# snappergps_board_2_1_0.net
KiCad netlist of a schematic drawn in EAGLE
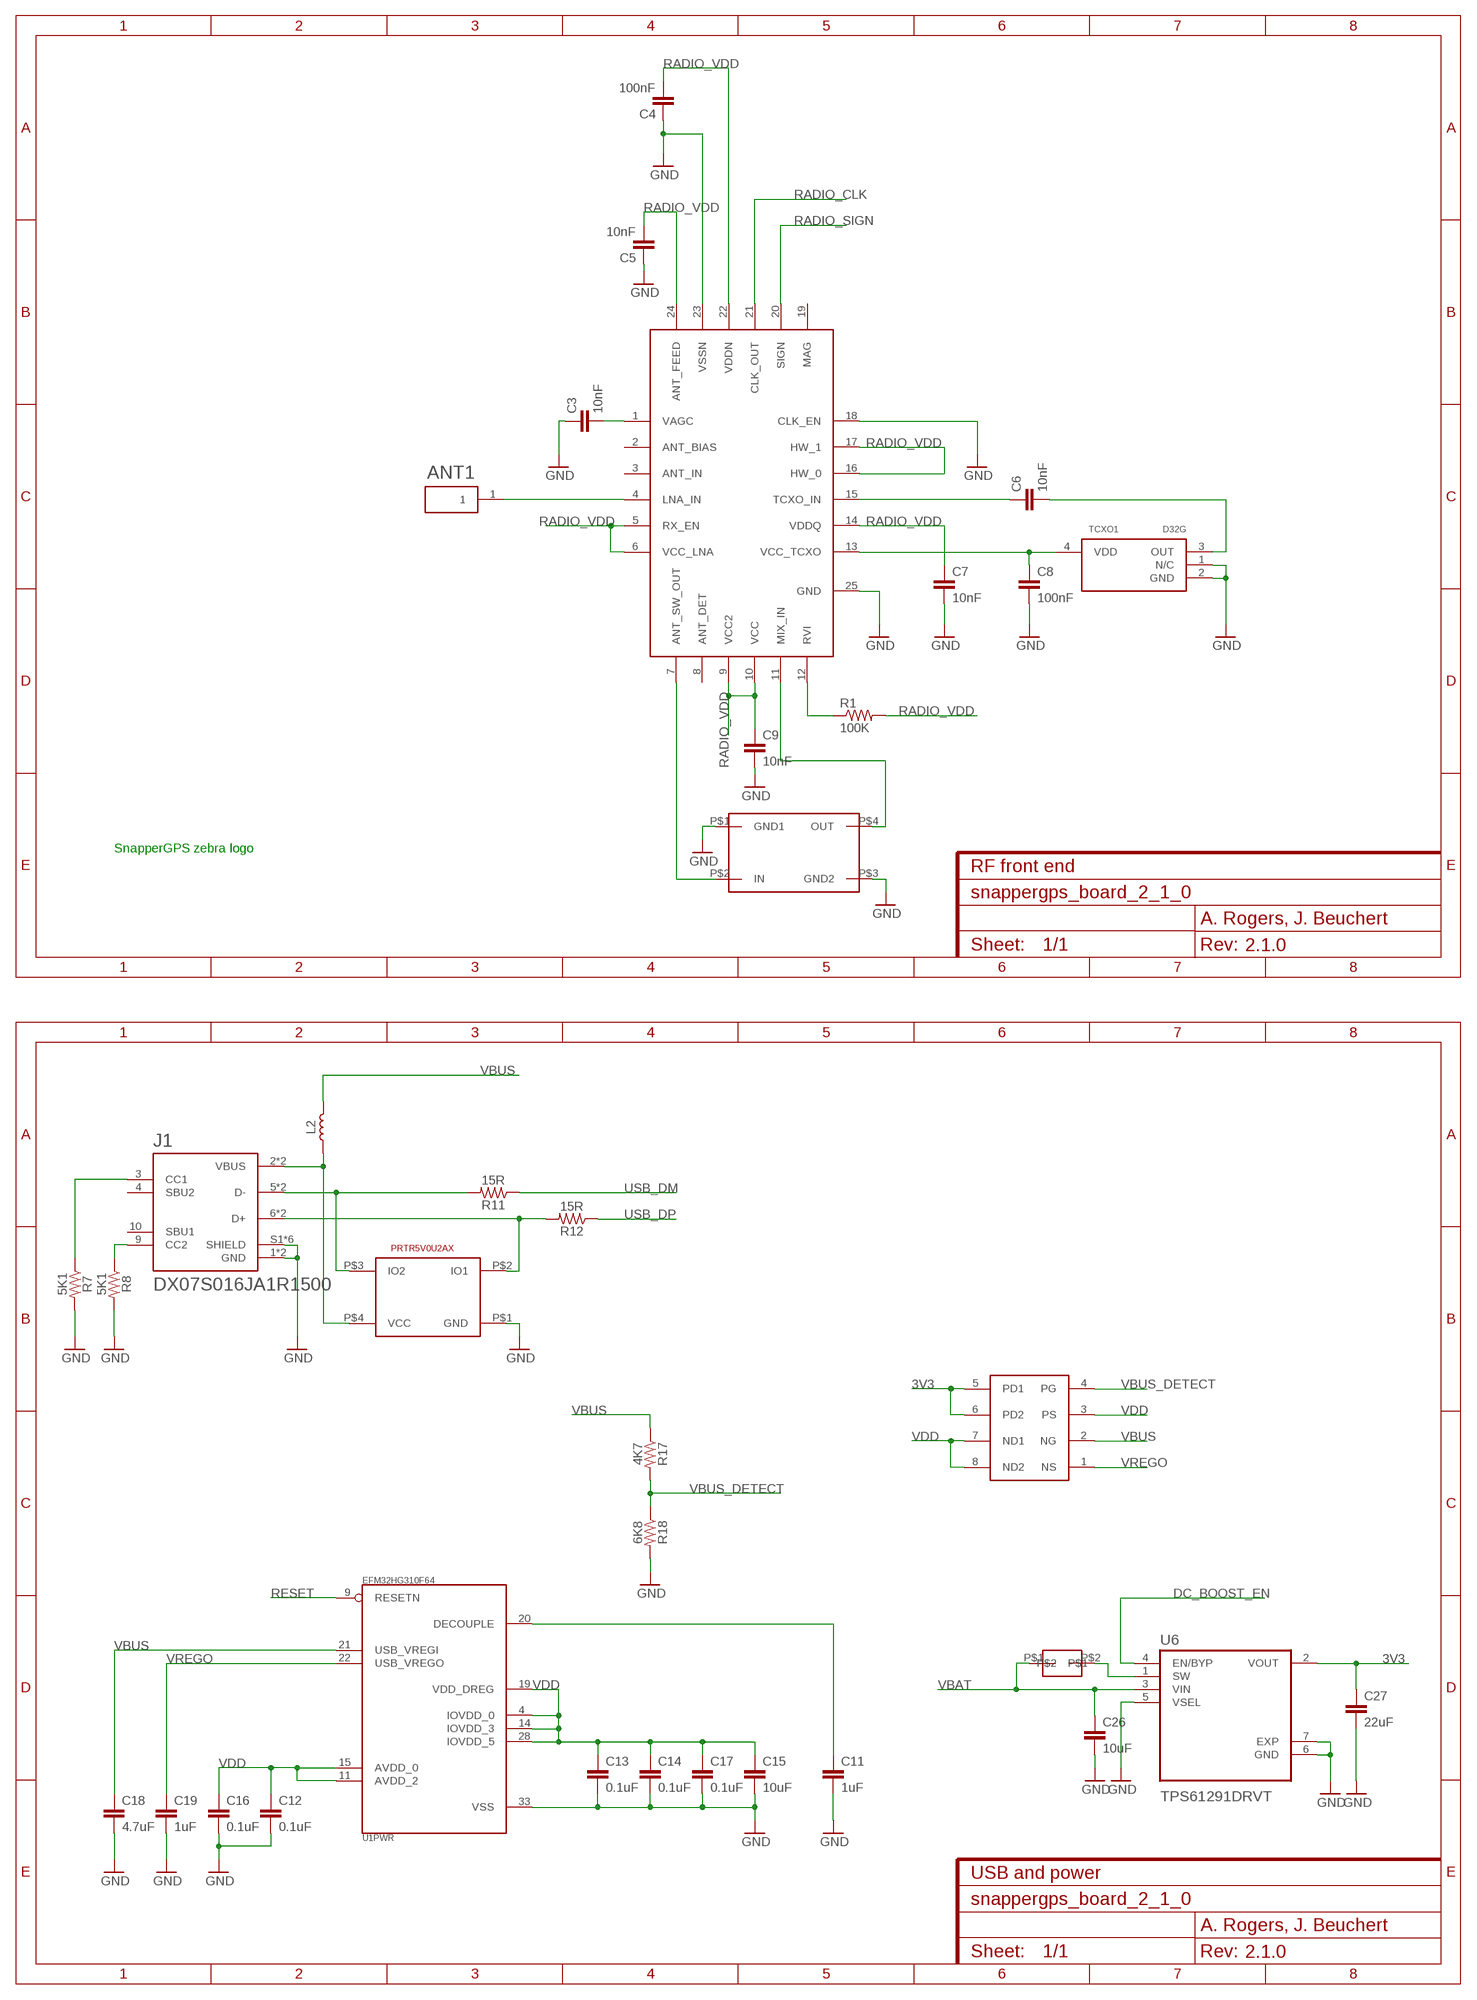
[diagram p0: schematic, sheet 1, part 1 of 2]
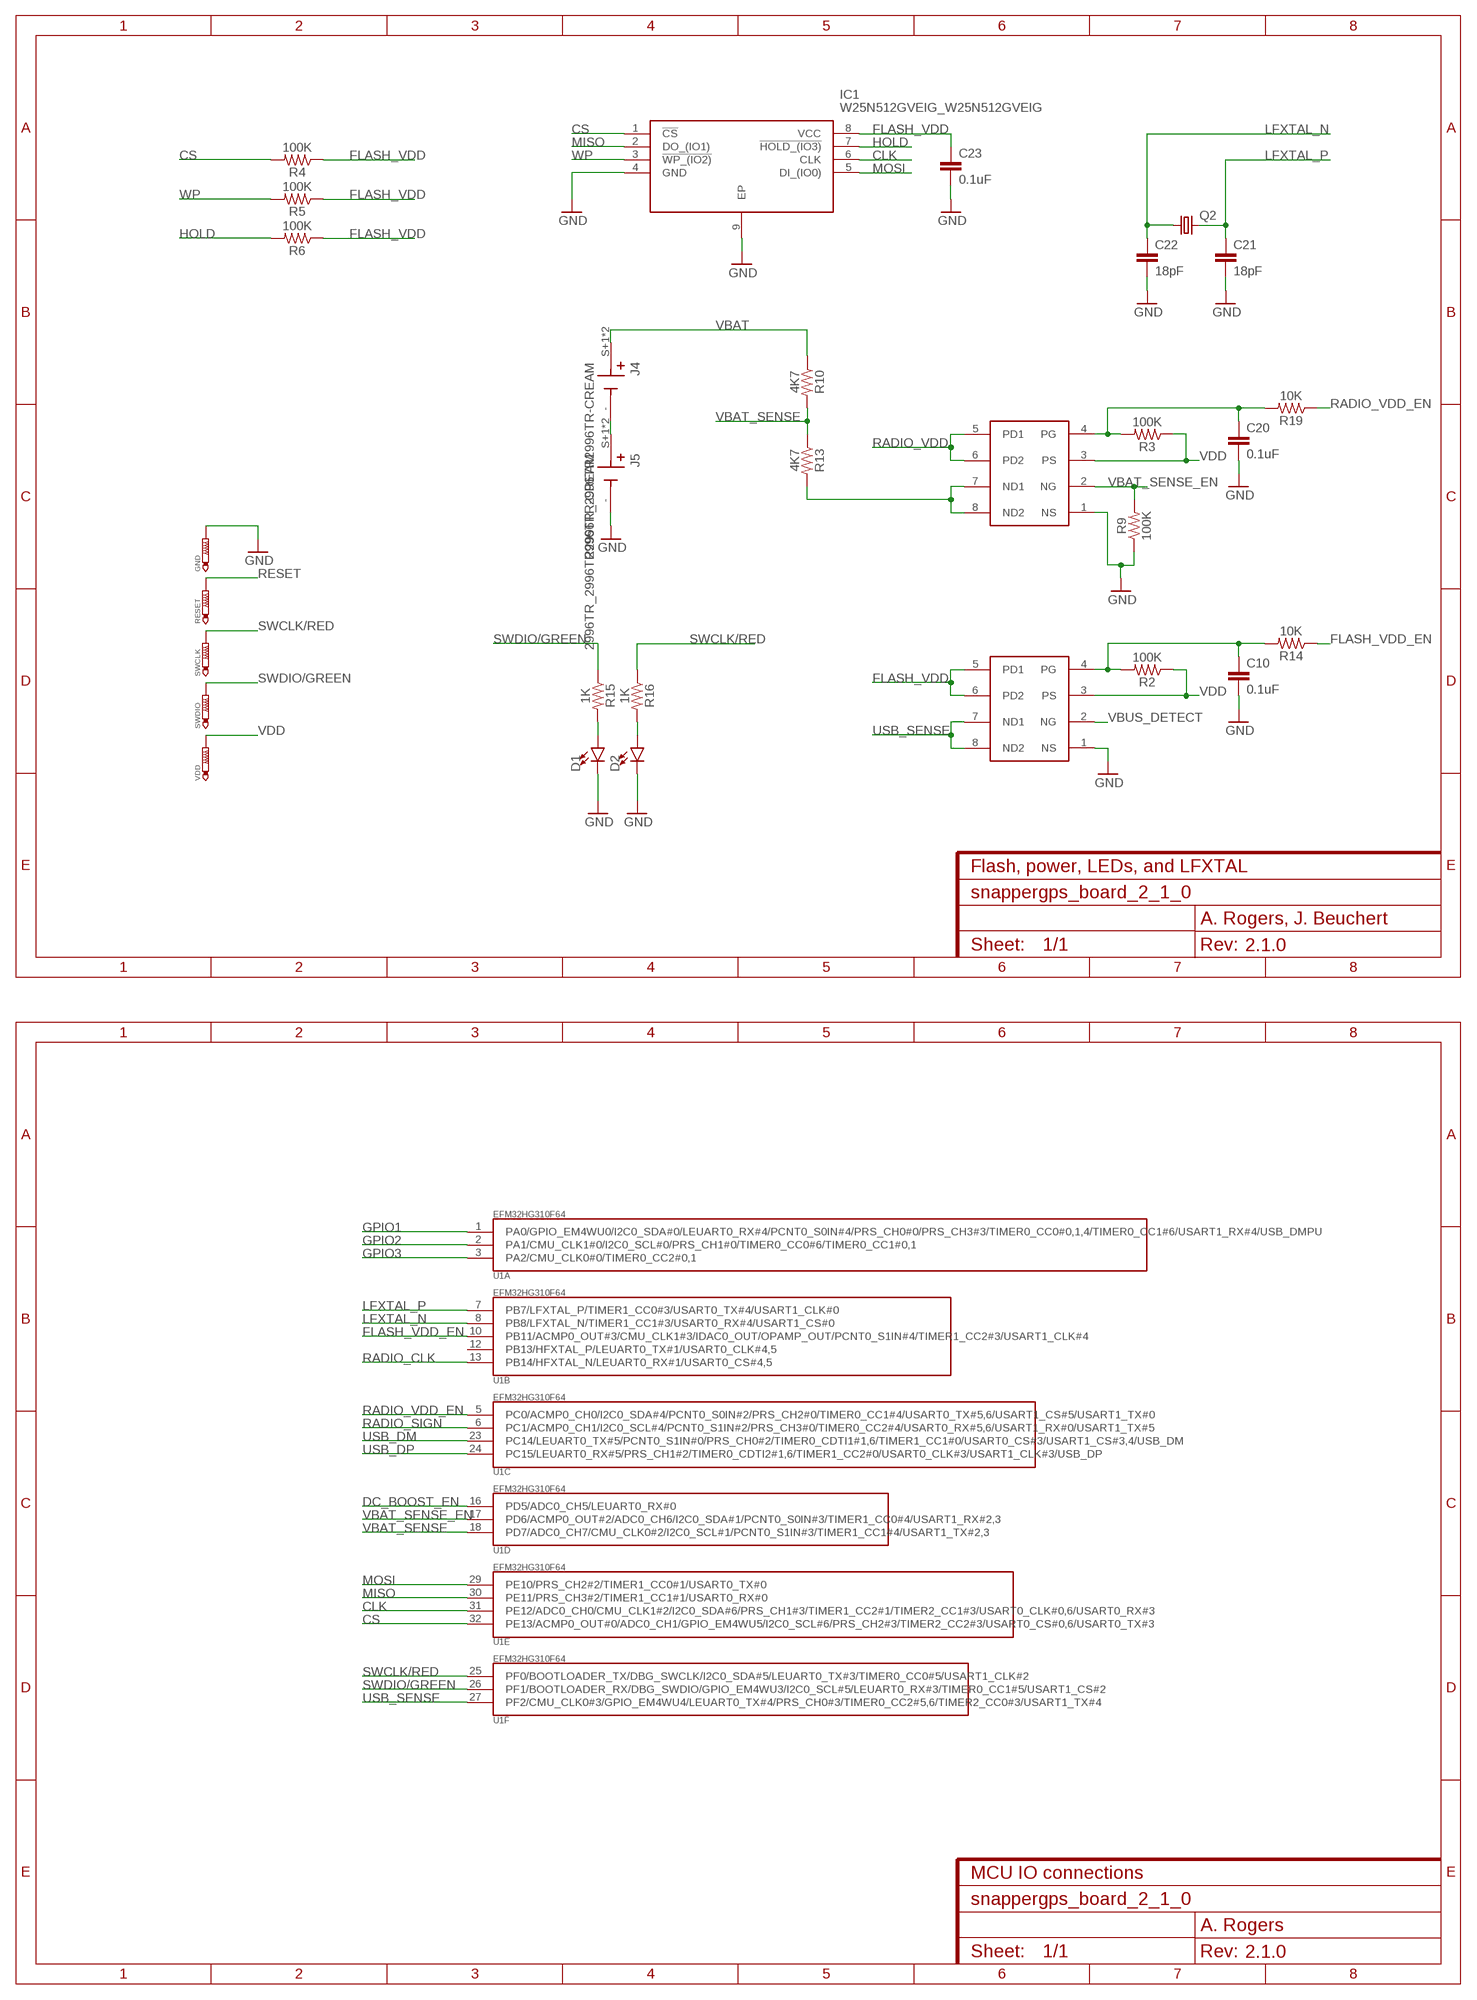
[diagram p1: schematic, sheet 1, part 2 of 2]

(export (version "E")
  (design (tool "Eeschema 10.0.6"))
  (components
    (comp (ref "ANT1")
      (value "GP.1575.25.2.A.02")
      (footprint "eagle-import:GP1575252A02")
      (fields (field (name "MOUSER_PART_NUMBER") "960-GP1575252A02"))
      (libsource (lib "eagle-import") (part "GP.1575.25.2.A.02"))
    )
    (comp (ref "C3")
      (value "10nF")
      (footprint "eagle-import:0402")
      (libsource (lib "eagle-import") (part "CAPACITOR_0402"))
    )
    (comp (ref "C4")
      (value "100nF")
      (footprint "eagle-import:0402")
      (libsource (lib "eagle-import") (part "CAPACITOR_0402"))
    )
    (comp (ref "C5")
      (value "10nF")
      (footprint "eagle-import:0402")
      (libsource (lib "eagle-import") (part "CAPACITOR_0402"))
    )
    (comp (ref "C6")
      (value "10nF")
      (footprint "eagle-import:0402")
      (libsource (lib "eagle-import") (part "CAPACITOR_0402"))
    )
    (comp (ref "C7")
      (value "10nF")
      (footprint "eagle-import:0402")
      (libsource (lib "eagle-import") (part "CAPACITOR_0402"))
    )
    (comp (ref "C8")
      (value "100nF")
      (footprint "eagle-import:0402")
      (libsource (lib "eagle-import") (part "CAPACITOR_0402"))
    )
    (comp (ref "C9")
      (value "10nF")
      (footprint "eagle-import:0402")
      (libsource (lib "eagle-import") (part "CAPACITOR_0402"))
    )
    (comp (ref "C10")
      (value "0.1uF")
      (footprint "eagle-import:0402")
      (libsource (lib "eagle-import") (part "CAPACITOR_0402"))
    )
    (comp (ref "C11")
      (value "1uF")
      (footprint "eagle-import:0603")
      (libsource (lib "eagle-import") (part "CAPACITOR_0603"))
    )
    (comp (ref "C12")
      (value "0.1uF")
      (footprint "eagle-import:0402")
      (libsource (lib "eagle-import") (part "CAPACITOR_0402"))
    )
    (comp (ref "C13")
      (value "0.1uF")
      (footprint "eagle-import:0402")
      (libsource (lib "eagle-import") (part "CAPACITOR_0402"))
    )
    (comp (ref "C14")
      (value "0.1uF")
      (footprint "eagle-import:0402")
      (libsource (lib "eagle-import") (part "CAPACITOR_0402"))
    )
    (comp (ref "C15")
      (value "10uF")
      (footprint "eagle-import:0603")
      (libsource (lib "eagle-import") (part "CAPACITOR_0603"))
    )
    (comp (ref "C16")
      (value "0.1uF")
      (footprint "eagle-import:0402")
      (libsource (lib "eagle-import") (part "CAPACITOR_0402"))
    )
    (comp (ref "C17")
      (value "0.1uF")
      (footprint "eagle-import:0402")
      (libsource (lib "eagle-import") (part "CAPACITOR_0402"))
    )
    (comp (ref "C18")
      (value "4.7uF")
      (footprint "eagle-import:0603")
      (libsource (lib "eagle-import") (part "CAPACITOR_0603"))
    )
    (comp (ref "C19")
      (value "1uF")
      (footprint "eagle-import:0603")
      (libsource (lib "eagle-import") (part "CAPACITOR_0603"))
    )
    (comp (ref "C20")
      (value "0.1uF")
      (footprint "eagle-import:0402")
      (libsource (lib "eagle-import") (part "CAPACITOR_0402"))
    )
    (comp (ref "C21")
      (value "18pF")
      (footprint "eagle-import:0402")
      (libsource (lib "eagle-import") (part "CAPACITOR_0402"))
    )
    (comp (ref "C22")
      (value "18pF")
      (footprint "eagle-import:0402")
      (libsource (lib "eagle-import") (part "CAPACITOR_0402"))
    )
    (comp (ref "C23")
      (value "0.1uF")
      (footprint "eagle-import:0402")
      (libsource (lib "eagle-import") (part "CAPACITOR_0402"))
    )
    (comp (ref "C26")
      (value "10uF")
      (footprint "eagle-import:C0603K")
      (libsource (lib "eagle-import") (part "C-EUC0603K"))
    )
    (comp (ref "C27")
      (value "22uF")
      (footprint "eagle-import:C0603K")
      (libsource (lib "eagle-import") (part "C-EUC0603K"))
    )
    (comp (ref "D1")
      (value "LED0603")
      (footprint "eagle-import:LED-0603")
      (libsource (lib "eagle-import") (part "LED0603"))
    )
    (comp (ref "D2")
      (value "LED0603")
      (footprint "eagle-import:LED-0603")
      (libsource (lib "eagle-import") (part "LED0603"))
    )
    (comp (ref "GND")
      (value "PTR1B1,27")
      (footprint "eagle-import:B1,27")
      (libsource (lib "eagle-import") (part "PTR1B1,27"))
    )
    (comp (ref "IC1")
      (value "W25N512GVEIG_W25N512GVEIG")
      (footprint "eagle-import:W25N512GVEIG_SON127P800X600X80-9N")
      (fields
        (field (name "MANUFACTURER_PART_NUMBER") "W25N512GVEIG")
        (field (name "MOUSER_PART_NUMBER") "454-W25N512GVEIG")
      )
      (libsource (lib "eagle-import") (part "W25N512GVEIG_W25N512GVEIG"))
    )
    (comp (ref "J1")
      (value "DX07S016JA1R1500")
      (footprint "eagle-import:JAE_DX07S016JA1R1500")
      (fields (field (name "MF") "JAE Electronics"))
      (libsource (lib "eagle-import") (part "DX07S016JA1R1500"))
    )
    (comp (ref "J4")
      (value "2996TR_2996TR2996TR-CREAM")
      (footprint "eagle-import:2996TR_BAT_2996TR")
      (fields (field (name "MF") "Keystone Electronics") (field (name "MP") "2996TR"))
      (libsource (lib "eagle-import") (part "2996TR_2996TR2996TR-CREAM"))
    )
    (comp (ref "J5")
      (value "2996TR_2996TR2996TR-CREAM")
      (footprint "eagle-import:2996TR_BAT_2996TR")
      (fields (field (name "MF") "Keystone Electronics") (field (name "MP") "2996TR"))
      (libsource (lib "eagle-import") (part "2996TR_2996TR2996TR-CREAM"))
    )
    (comp (ref "L2")
      (value "INDUCTOR")
      (footprint "eagle-import:0402")
      (libsource (lib "eagle-import") (part "INDUCTOR"))
    )
    (comp (ref "Q1")
      (value "TT8M1TRAMANDA")
      (footprint "eagle-import:AMANDA_TSST8")
      (libsource (lib "eagle-import") (part "TT8M1TRAMANDA"))
    )
    (comp (ref "Q2")
      (value "CRYSTAL_JTX310")
      (footprint "eagle-import:3.2X1.5")
      (libsource (lib "eagle-import") (part "CRYSTAL_JTX310"))
    )
    (comp (ref "Q3")
      (value "TT8M1TRAMANDA")
      (footprint "eagle-import:AMANDA_TSST8")
      (libsource (lib "eagle-import") (part "TT8M1TRAMANDA"))
    )
    (comp (ref "Q4")
      (value "TT8M1TRAMANDA")
      (footprint "eagle-import:AMANDA_TSST8")
      (libsource (lib "eagle-import") (part "TT8M1TRAMANDA"))
    )
    (comp (ref "R1")
      (value "100K")
      (footprint "eagle-import:0402")
      (libsource (lib "eagle-import") (part "RESISTOR_0402"))
    )
    (comp (ref "R2")
      (value "100K")
      (footprint "eagle-import:0402")
      (libsource (lib "eagle-import") (part "RESISTOR_0402"))
    )
    (comp (ref "R3")
      (value "100K")
      (footprint "eagle-import:0402")
      (libsource (lib "eagle-import") (part "RESISTOR_0402"))
    )
    (comp (ref "R4")
      (value "100K")
      (footprint "eagle-import:0402")
      (libsource (lib "eagle-import") (part "RESISTOR_0402"))
    )
    (comp (ref "R5")
      (value "100K")
      (footprint "eagle-import:0402")
      (libsource (lib "eagle-import") (part "RESISTOR_0402"))
    )
    (comp (ref "R6")
      (value "100K")
      (footprint "eagle-import:0402")
      (libsource (lib "eagle-import") (part "RESISTOR_0402"))
    )
    (comp (ref "R7")
      (value "5K1")
      (footprint "eagle-import:0402")
      (libsource (lib "eagle-import") (part "RESISTOR_0402"))
    )
    (comp (ref "R8")
      (value "5K1")
      (footprint "eagle-import:0402")
      (libsource (lib "eagle-import") (part "RESISTOR_0402"))
    )
    (comp (ref "R9")
      (value "100K")
      (footprint "eagle-import:0402")
      (libsource (lib "eagle-import") (part "RESISTOR_0402"))
    )
    (comp (ref "R10")
      (value "4K7")
      (footprint "eagle-import:0402")
      (libsource (lib "eagle-import") (part "RESISTOR_0402"))
    )
    (comp (ref "R11")
      (value "15R")
      (footprint "eagle-import:0402")
      (libsource (lib "eagle-import") (part "RESISTOR_0402"))
    )
    (comp (ref "R12")
      (value "15R")
      (footprint "eagle-import:0402")
      (libsource (lib "eagle-import") (part "RESISTOR_0402"))
    )
    (comp (ref "R13")
      (value "4K7")
      (footprint "eagle-import:0402")
      (libsource (lib "eagle-import") (part "RESISTOR_0402"))
    )
    (comp (ref "R14")
      (value "10K")
      (footprint "eagle-import:0402")
      (libsource (lib "eagle-import") (part "RESISTOR_0402"))
    )
    (comp (ref "R15")
      (value "1K")
      (footprint "eagle-import:0402")
      (libsource (lib "eagle-import") (part "RESISTOR_0402"))
    )
    (comp (ref "R16")
      (value "1K")
      (footprint "eagle-import:0402")
      (libsource (lib "eagle-import") (part "RESISTOR_0402"))
    )
    (comp (ref "R17")
      (value "4K7")
      (footprint "eagle-import:0402")
      (libsource (lib "eagle-import") (part "RESISTOR_0402"))
    )
    (comp (ref "R18")
      (value "6K8")
      (footprint "eagle-import:0402")
      (libsource (lib "eagle-import") (part "RESISTOR_0402"))
    )
    (comp (ref "R19")
      (value "10K")
      (footprint "eagle-import:0402")
      (libsource (lib "eagle-import") (part "RESISTOR_0402"))
    )
    (comp (ref "RESET")
      (value "PTR1B1,27")
      (footprint "eagle-import:B1,27")
      (libsource (lib "eagle-import") (part "PTR1B1,27"))
    )
    (comp (ref "SAW1")
      (value "SAW_FILTER")
      (footprint "eagle-import:SAW_FILTER")
      (libsource (lib "eagle-import") (part "SAW_FILTER"))
    )
    (comp (ref "SWCLK")
      (value "PTR1B1,27")
      (footprint "eagle-import:B1,27")
      (libsource (lib "eagle-import") (part "PTR1B1,27"))
    )
    (comp (ref "SWDIO")
      (value "PTR1B1,27")
      (footprint "eagle-import:B1,27")
      (libsource (lib "eagle-import") (part "PTR1B1,27"))
    )
    (comp (ref "TCXO1")
      (value "D32G")
      (footprint "eagle-import:D32G")
      (libsource (lib "eagle-import") (part "D32G"))
    )
    (comp (ref "U1")
      (value "EFM32HG310F64")
      (footprint "eagle-import:QFN32")
      (libsource (lib "eagle-import") (part "EFM32HG310F64"))
    )
    (comp (ref "U2")
      (value "RF_CIRCUIT-SE4150L")
      (footprint "eagle-import:QFN50P400X400X90-25N")
      (libsource (lib "eagle-import") (part "RF_CIRCUIT-SE4150L"))
    )
    (comp (ref "U3")
      (value "TVS_DIODE-PRTR5V0U2AX")
      (footprint "eagle-import:TVS_DIODE-PRTR5V0U2AX")
      (libsource (lib "eagle-import") (part "TVS_DIODE-PRTR5V0U2AX"))
    )
    (comp (ref "U6")
      (value "TPS61291DRVT")
      (footprint "eagle-import:SON65P200X200X80-7N")
      (fields (field (name "MF") "Texas Instruments"))
      (libsource (lib "eagle-import") (part "TPS61291DRVT"))
    )
    (comp (ref "U7")
      (value "MDMK2020T3R3MM")
      (footprint "eagle-import:MDMK2020T3R3MM")
      (libsource (lib "eagle-import") (part "MDMK2020T3R3MM"))
    )
    (comp (ref "VDD")
      (value "PTR1B1,27")
      (footprint "eagle-import:B1,27")
      (libsource (lib "eagle-import") (part "PTR1B1,27"))
    )
  )
  (nets
    (net (code "1") (name "/3V3") (class "Default")
      (node (ref "C27") (pin "1") (pinfunction "1_1") (pintype "passive"))
      (node (ref "Q4") (pin "5") (pinfunction "PD1_5") (pintype "bidirectional"))
      (node (ref "Q4") (pin "6") (pinfunction "PD2_6") (pintype "bidirectional"))
      (node (ref "U6") (pin "2") (pinfunction "VOUT_2") (pintype "output"))
    )
    (net (code "2") (name "/CLK") (class "Default")
      (node (ref "IC1") (pin "6") (pinfunction "CLK_6") (pintype "bidirectional"))
      (node (ref "U1") (pin "31") (pinfunction "PE12/ADC0_CH0/CMU_CLK1#2/I2C0_SDA#6/PRS_CH1#3/TIMER1_CC2#1/TIMER2_CC1#3/USART0_CLK#0,6/USART0_RX#3_31") (pintype "bidirectional"))
    )
    (net (code "3") (name "/CS") (class "Default")
      (node (ref "IC1") (pin "1") (pinfunction "~{CS}_1") (pintype "bidirectional"))
      (node (ref "R4") (pin "2") (pinfunction "2_2") (pintype "passive"))
      (node (ref "U1") (pin "32") (pinfunction "PE13/ACMP0_OUT#0/ADC0_CH1/GPIO_EM4WU5/I2C0_SCL#6/PRS_CH2#3/TIMER2_CC2#3/USART0_CS#0,6/USART0_TX#3_32") (pintype "bidirectional"))
    )
    (net (code "4") (name "/DC_BOOST_EN") (class "Default")
      (node (ref "U1") (pin "16") (pinfunction "PD5/ADC0_CH5/LEUART0_RX#0_16") (pintype "bidirectional"))
      (node (ref "U6") (pin "4") (pinfunction "EN/BYP_4") (pintype "input"))
    )
    (net (code "5") (name "/FLASH_VDD") (class "Default")
      (node (ref "C23") (pin "1") (pinfunction "1_1") (pintype "passive"))
      (node (ref "IC1") (pin "8") (pinfunction "VCC_8") (pintype "bidirectional"))
      (node (ref "Q3") (pin "5") (pinfunction "PD1_5") (pintype "bidirectional"))
      (node (ref "Q3") (pin "6") (pinfunction "PD2_6") (pintype "bidirectional"))
      (node (ref "R4") (pin "1") (pinfunction "1_1") (pintype "passive"))
      (node (ref "R5") (pin "1") (pinfunction "1_1") (pintype "passive"))
      (node (ref "R6") (pin "1") (pinfunction "1_1") (pintype "passive"))
    )
    (net (code "6") (name "/FLASH_VDD_EN") (class "Default")
      (node (ref "R14") (pin "1") (pinfunction "1_1") (pintype "passive"))
      (node (ref "U1") (pin "10") (pinfunction "PB11/ACMP0_OUT#3/CMU_CLK1#3/IDAC0_OUT/OPAMP_OUT/PCNT0_S1IN#4/TIMER1_CC2#3/USART1_CLK#4_10") (pintype "bidirectional"))
    )
    (net (code "7") (name "/GPIO1") (class "Default")
      (node (ref "U1") (pin "1") (pinfunction "PA0/GPIO_EM4WU0/I2C0_SDA#0/LEUART0_RX#4/PCNT0_S0IN#4/PRS_CH0#0/PRS_CH3#3/TIMER0_CC0#0,1,4/TIMER0_CC1#6/USART1_RX#4/USB_DMPU_1") (pintype "bidirectional"))
    )
    (net (code "8") (name "/GPIO2") (class "Default")
      (node (ref "U1") (pin "2") (pinfunction "PA1/CMU_CLK1#0/I2C0_SCL#0/PRS_CH1#0/TIMER0_CC0#6/TIMER0_CC1#0,1_2") (pintype "bidirectional"))
    )
    (net (code "9") (name "/GPIO3") (class "Default")
      (node (ref "U1") (pin "3") (pinfunction "PA2/CMU_CLK0#0/TIMER0_CC2#0,1_3") (pintype "bidirectional"))
    )
    (net (code "10") (name "/HOLD") (class "Default")
      (node (ref "IC1") (pin "7") (pinfunction "~{HOLD_(IO3})_7") (pintype "bidirectional"))
      (node (ref "R6") (pin "2") (pinfunction "2_2") (pintype "passive"))
    )
    (net (code "11") (name "/LFXTAL_N") (class "Default")
      (node (ref "C22") (pin "1") (pinfunction "1_1") (pintype "passive"))
      (node (ref "Q2") (pin "1") (pinfunction "1_1") (pintype "passive"))
      (node (ref "U1") (pin "8") (pinfunction "PB8/LFXTAL_N/TIMER1_CC1#3/USART0_RX#4/USART1_CS#0_8") (pintype "bidirectional"))
    )
    (net (code "12") (name "/LFXTAL_P") (class "Default")
      (node (ref "C21") (pin "1") (pinfunction "1_1") (pintype "passive"))
      (node (ref "Q2") (pin "2") (pinfunction "2_2") (pintype "passive"))
      (node (ref "U1") (pin "7") (pinfunction "PB7/LFXTAL_P/TIMER1_CC0#3/USART0_TX#4/USART1_CLK#0_7") (pintype "bidirectional"))
    )
    (net (code "13") (name "/MISO") (class "Default")
      (node (ref "IC1") (pin "2") (pinfunction "DO_(IO1)_2") (pintype "bidirectional"))
      (node (ref "U1") (pin "30") (pinfunction "PE11/PRS_CH3#2/TIMER1_CC1#1/USART0_RX#0_30") (pintype "bidirectional"))
    )
    (net (code "14") (name "/MOSI") (class "Default")
      (node (ref "IC1") (pin "5") (pinfunction "DI_(IO0)_5") (pintype "bidirectional"))
      (node (ref "U1") (pin "29") (pinfunction "PE10/PRS_CH2#2/TIMER1_CC0#1/USART0_TX#0_29") (pintype "bidirectional"))
    )
    (net (code "15") (name "/RADIO_CLK") (class "Default")
      (node (ref "U1") (pin "13") (pinfunction "PB14/HFXTAL_N/LEUART0_RX#1/USART0_CS#4,5_13") (pintype "bidirectional"))
      (node (ref "U2") (pin "21") (pinfunction "CLK_OUT_21") (pintype "bidirectional"))
    )
    (net (code "16") (name "/RADIO_SIGN") (class "Default")
      (node (ref "U1") (pin "6") (pinfunction "PC1/ACMP0_CH1/I2C0_SCL#4/PCNT0_S1IN#2/PRS_CH3#0/TIMER0_CC2#4/USART0_RX#5,6/USART1_RX#0/USART1_TX#5_6") (pintype "bidirectional"))
      (node (ref "U2") (pin "20") (pinfunction "SIGN_20") (pintype "bidirectional"))
    )
    (net (code "17") (name "/RADIO_VDD") (class "Default")
      (node (ref "C4") (pin "2") (pinfunction "2_2") (pintype "passive"))
      (node (ref "C5") (pin "2") (pinfunction "2_2") (pintype "passive"))
      (node (ref "C7") (pin "1") (pinfunction "1_1") (pintype "passive"))
      (node (ref "C9") (pin "1") (pinfunction "1_1") (pintype "passive"))
      (node (ref "Q1") (pin "5") (pinfunction "PD1_5") (pintype "bidirectional"))
      (node (ref "Q1") (pin "6") (pinfunction "PD2_6") (pintype "bidirectional"))
      (node (ref "R1") (pin "2") (pinfunction "2_2") (pintype "passive"))
      (node (ref "U2") (pin "10") (pinfunction "VCC_10") (pintype "bidirectional"))
      (node (ref "U2") (pin "14") (pinfunction "VDDQ_14") (pintype "bidirectional"))
      (node (ref "U2") (pin "16") (pinfunction "HW_0_16") (pintype "bidirectional"))
      (node (ref "U2") (pin "17") (pinfunction "HW_1_17") (pintype "bidirectional"))
      (node (ref "U2") (pin "22") (pinfunction "VDDN_22") (pintype "bidirectional"))
      (node (ref "U2") (pin "24") (pinfunction "ANT_FEED_24") (pintype "bidirectional"))
      (node (ref "U2") (pin "5") (pinfunction "RX_EN_5") (pintype "bidirectional"))
      (node (ref "U2") (pin "6") (pinfunction "VCC_LNA_6") (pintype "bidirectional"))
      (node (ref "U2") (pin "9") (pinfunction "VCC2_9") (pintype "bidirectional"))
    )
    (net (code "18") (name "/RADIO_VDD_EN") (class "Default")
      (node (ref "R19") (pin "1") (pinfunction "1_1") (pintype "passive"))
      (node (ref "U1") (pin "5") (pinfunction "PC0/ACMP0_CH0/I2C0_SDA#4/PCNT0_S0IN#2/PRS_CH2#0/TIMER0_CC1#4/USART0_TX#5,6/USART1_CS#5/USART1_TX#0_5") (pintype "bidirectional"))
    )
    (net (code "19") (name "/RESET") (class "Default")
      (node (ref "RESET") (pin "TP") (pinfunction "TP_TP") (pintype "input"))
      (node (ref "U1") (pin "9") (pinfunction "RESETN_9") (pintype "passive"))
    )
    (net (code "20") (name "/SWCLK{slash}RED") (class "Default")
      (node (ref "R16") (pin "1") (pinfunction "1_1") (pintype "passive"))
      (node (ref "SWCLK") (pin "TP") (pinfunction "TP_TP") (pintype "input"))
      (node (ref "U1") (pin "25") (pinfunction "PF0/BOOTLOADER_TX/DBG_SWCLK/I2C0_SDA#5/LEUART0_TX#3/TIMER0_CC0#5/USART1_CLK#2_25") (pintype "bidirectional"))
    )
    (net (code "21") (name "/SWDIO{slash}GREEN") (class "Default")
      (node (ref "R15") (pin "1") (pinfunction "1_1") (pintype "passive"))
      (node (ref "SWDIO") (pin "TP") (pinfunction "TP_TP") (pintype "input"))
      (node (ref "U1") (pin "26") (pinfunction "PF1/BOOTLOADER_RX/DBG_SWDIO/GPIO_EM4WU3/I2C0_SCL#5/LEUART0_RX#3/TIMER0_CC1#5/USART1_CS#2_26") (pintype "bidirectional"))
    )
    (net (code "22") (name "/USB_DM") (class "Default")
      (node (ref "R11") (pin "1") (pinfunction "1_1") (pintype "passive"))
      (node (ref "U1") (pin "23") (pinfunction "PC14/LEUART0_TX#5/PCNT0_S1IN#0/PRS_CH0#2/TIMER0_CDTI1#1,6/TIMER1_CC1#0/USART0_CS#3/USART1_CS#3,4/USB_DM_23") (pintype "bidirectional"))
    )
    (net (code "23") (name "/USB_DP") (class "Default")
      (node (ref "R12") (pin "1") (pinfunction "1_1") (pintype "passive"))
      (node (ref "U1") (pin "24") (pinfunction "PC15/LEUART0_RX#5/PRS_CH1#2/TIMER0_CDTI2#1,6/TIMER1_CC2#0/USART0_CLK#3/USART1_CLK#3/USB_DP_24") (pintype "bidirectional"))
    )
    (net (code "24") (name "/USB_SENSE") (class "Default")
      (node (ref "Q3") (pin "7") (pinfunction "ND1_7") (pintype "bidirectional"))
      (node (ref "Q3") (pin "8") (pinfunction "ND2_8") (pintype "bidirectional"))
      (node (ref "U1") (pin "27") (pinfunction "PF2/CMU_CLK0#3/GPIO_EM4WU4/LEUART0_TX#4/PRS_CH0#3/TIMER0_CC2#5,6/TIMER2_CC0#3/USART1_TX#4_27") (pintype "bidirectional"))
    )
    (net (code "25") (name "/VBAT") (class "Default")
      (node (ref "C26") (pin "1") (pinfunction "1_1") (pintype "passive"))
      (node (ref "J4") (pin "S+1") (pinfunction "+_S+1") (pintype "passive"))
      (node (ref "J4") (pin "S+2") (pinfunction "+_S+2") (pintype "passive"))
      (node (ref "R10") (pin "1") (pinfunction "1_1") (pintype "passive"))
      (node (ref "U6") (pin "3") (pinfunction "VIN_3") (pintype "input"))
      (node (ref "U7") (pin "P$1") (pinfunction "P$1_P$1") (pintype "bidirectional"))
    )
    (net (code "26") (name "/VBAT_SENSE") (class "Default")
      (node (ref "R10") (pin "2") (pinfunction "2_2") (pintype "passive"))
      (node (ref "R13") (pin "1") (pinfunction "1_1") (pintype "passive"))
      (node (ref "U1") (pin "18") (pinfunction "PD7/ADC0_CH7/CMU_CLK0#2/I2C0_SCL#1/PCNT0_S1IN#3/TIMER1_CC1#4/USART1_TX#2,3_18") (pintype "bidirectional"))
    )
    (net (code "27") (name "/VBAT_SENSE_EN") (class "Default")
      (node (ref "Q1") (pin "2") (pinfunction "NG_2") (pintype "bidirectional"))
      (node (ref "R9") (pin "2") (pinfunction "2_2") (pintype "passive"))
      (node (ref "U1") (pin "17") (pinfunction "PD6/ACMP0_OUT#2/ADC0_CH6/I2C0_SDA#1/PCNT0_S0IN#3/TIMER1_CC0#4/USART1_RX#2,3_17") (pintype "bidirectional"))
    )
    (net (code "28") (name "/VBUS") (class "Default")
      (node (ref "C18") (pin "1") (pinfunction "1_1") (pintype "passive"))
      (node (ref "L2") (pin "2") (pinfunction "2_2") (pintype "passive"))
      (node (ref "Q4") (pin "2") (pinfunction "NG_2") (pintype "bidirectional"))
      (node (ref "R17") (pin "1") (pinfunction "1_1") (pintype "passive"))
      (node (ref "U1") (pin "21") (pinfunction "USB_VREGI_21") (pintype "power_in"))
    )
    (net (code "29") (name "/VBUS_DETECT") (class "Default")
      (node (ref "Q3") (pin "2") (pinfunction "NG_2") (pintype "bidirectional"))
      (node (ref "Q4") (pin "4") (pinfunction "PG_4") (pintype "bidirectional"))
      (node (ref "R17") (pin "2") (pinfunction "2_2") (pintype "passive"))
      (node (ref "R18") (pin "1") (pinfunction "1_1") (pintype "passive"))
    )
    (net (code "30") (name "/VDD") (class "Default")
      (node (ref "C12") (pin "1") (pinfunction "1_1") (pintype "passive"))
      (node (ref "C13") (pin "1") (pinfunction "1_1") (pintype "passive"))
      (node (ref "C14") (pin "1") (pinfunction "1_1") (pintype "passive"))
      (node (ref "C15") (pin "1") (pinfunction "1_1") (pintype "passive"))
      (node (ref "C16") (pin "1") (pinfunction "1_1") (pintype "passive"))
      (node (ref "C17") (pin "1") (pinfunction "1_1") (pintype "passive"))
      (node (ref "Q1") (pin "3") (pinfunction "PS_3") (pintype "bidirectional"))
      (node (ref "Q3") (pin "3") (pinfunction "PS_3") (pintype "bidirectional"))
      (node (ref "Q4") (pin "3") (pinfunction "PS_3") (pintype "bidirectional"))
      (node (ref "Q4") (pin "7") (pinfunction "ND1_7") (pintype "bidirectional"))
      (node (ref "Q4") (pin "8") (pinfunction "ND2_8") (pintype "bidirectional"))
      (node (ref "R2") (pin "1") (pinfunction "1_1") (pintype "passive"))
      (node (ref "R3") (pin "1") (pinfunction "1_1") (pintype "passive"))
      (node (ref "U1") (pin "11") (pinfunction "AVDD_2_11") (pintype "power_in"))
      (node (ref "U1") (pin "14") (pinfunction "IOVDD_3_14") (pintype "power_in"))
      (node (ref "U1") (pin "15") (pinfunction "AVDD_0_15") (pintype "power_in"))
      (node (ref "U1") (pin "19") (pinfunction "VDD_DREG_19") (pintype "power_in"))
      (node (ref "U1") (pin "28") (pinfunction "IOVDD_5_28") (pintype "power_in"))
      (node (ref "U1") (pin "4") (pinfunction "IOVDD_0_4") (pintype "power_in"))
      (node (ref "VDD") (pin "TP") (pinfunction "TP_TP") (pintype "input"))
    )
    (net (code "31") (name "/VREGO") (class "Default")
      (node (ref "C19") (pin "1") (pinfunction "1_1") (pintype "passive"))
      (node (ref "Q4") (pin "1") (pinfunction "NS_1") (pintype "bidirectional"))
      (node (ref "U1") (pin "22") (pinfunction "USB_VREGO_22") (pintype "power_in"))
    )
    (net (code "32") (name "/WP") (class "Default")
      (node (ref "IC1") (pin "3") (pinfunction "~{WP_(IO2})_3") (pintype "bidirectional"))
      (node (ref "R5") (pin "2") (pinfunction "2_2") (pintype "passive"))
    )
    (net (code "33") (name "GND") (class "Default")
      (node (ref "C10") (pin "2") (pinfunction "2_2") (pintype "passive"))
      (node (ref "C11") (pin "2") (pinfunction "2_2") (pintype "passive"))
      (node (ref "C12") (pin "2") (pinfunction "2_2") (pintype "passive"))
      (node (ref "C13") (pin "2") (pinfunction "2_2") (pintype "passive"))
      (node (ref "C14") (pin "2") (pinfunction "2_2") (pintype "passive"))
      (node (ref "C15") (pin "2") (pinfunction "2_2") (pintype "passive"))
      (node (ref "C16") (pin "2") (pinfunction "2_2") (pintype "passive"))
      (node (ref "C17") (pin "2") (pinfunction "2_2") (pintype "passive"))
      (node (ref "C18") (pin "2") (pinfunction "2_2") (pintype "passive"))
      (node (ref "C19") (pin "2") (pinfunction "2_2") (pintype "passive"))
      (node (ref "C20") (pin "2") (pinfunction "2_2") (pintype "passive"))
      (node (ref "C21") (pin "2") (pinfunction "2_2") (pintype "passive"))
      (node (ref "C22") (pin "2") (pinfunction "2_2") (pintype "passive"))
      (node (ref "C23") (pin "2") (pinfunction "2_2") (pintype "passive"))
      (node (ref "C26") (pin "2") (pinfunction "2_2") (pintype "passive"))
      (node (ref "C27") (pin "2") (pinfunction "2_2") (pintype "passive"))
      (node (ref "C3") (pin "1") (pinfunction "1_1") (pintype "passive"))
      (node (ref "C4") (pin "1") (pinfunction "1_1") (pintype "passive"))
      (node (ref "C5") (pin "1") (pinfunction "1_1") (pintype "passive"))
      (node (ref "C7") (pin "2") (pinfunction "2_2") (pintype "passive"))
      (node (ref "C8") (pin "2") (pinfunction "2_2") (pintype "passive"))
      (node (ref "C9") (pin "2") (pinfunction "2_2") (pintype "passive"))
      (node (ref "D1") (pin "C") (pinfunction "C_C") (pintype "passive"))
      (node (ref "D2") (pin "C") (pinfunction "C_C") (pintype "passive"))
      (node (ref "GND") (pin "TP") (pinfunction "TP_TP") (pintype "input"))
      (node (ref "IC1") (pin "4") (pinfunction "GND_4") (pintype "bidirectional"))
      (node (ref "IC1") (pin "9") (pinfunction "EP_9") (pintype "bidirectional"))
      (node (ref "J1") (pin "1") (pinfunction "GND_1") (pintype "power_in"))
      (node (ref "J1") (pin "12") (pinfunction "GND_12") (pintype "power_in"))
      (node (ref "J1") (pin "S1") (pinfunction "SHIELD_S1") (pintype "passive"))
      (node (ref "J1") (pin "S2") (pinfunction "SHIELD_S2") (pintype "passive"))
      (node (ref "J1") (pin "S3") (pinfunction "SHIELD_S3") (pintype "passive"))
      (node (ref "J1") (pin "S4") (pinfunction "SHIELD_S4") (pintype "passive"))
      (node (ref "J1") (pin "S5") (pinfunction "SHIELD_S5") (pintype "passive"))
      (node (ref "J1") (pin "S6") (pinfunction "SHIELD_S6") (pintype "passive"))
      (node (ref "J5") (pin "-") (pinfunction "-_-") (pintype "passive"))
      (node (ref "Q1") (pin "1") (pinfunction "NS_1") (pintype "bidirectional"))
      (node (ref "Q3") (pin "1") (pinfunction "NS_1") (pintype "bidirectional"))
      (node (ref "R18") (pin "2") (pinfunction "2_2") (pintype "passive"))
      (node (ref "R7") (pin "2") (pinfunction "2_2") (pintype "passive"))
      (node (ref "R8") (pin "2") (pinfunction "2_2") (pintype "passive"))
      (node (ref "R9") (pin "1") (pinfunction "1_1") (pintype "passive"))
      (node (ref "SAW1") (pin "P$1") (pinfunction "GND1_P$1") (pintype "bidirectional"))
      (node (ref "SAW1") (pin "P$3") (pinfunction "GND2_P$3") (pintype "bidirectional"))
      (node (ref "TCXO1") (pin "1") (pinfunction "N/C_1") (pintype "bidirectional"))
      (node (ref "TCXO1") (pin "2") (pinfunction "GND_2") (pintype "bidirectional"))
      (node (ref "U1") (pin "33") (pinfunction "VSS_33") (pintype "power_in"))
      (node (ref "U2") (pin "18") (pinfunction "CLK_EN_18") (pintype "bidirectional"))
      (node (ref "U2") (pin "23") (pinfunction "VSSN_23") (pintype "bidirectional"))
      (node (ref "U2") (pin "25") (pinfunction "GND_25") (pintype "bidirectional"))
      (node (ref "U3") (pin "P$1") (pinfunction "GND_P$1") (pintype "bidirectional"))
      (node (ref "U6") (pin "5") (pinfunction "VSEL_5") (pintype "input"))
      (node (ref "U6") (pin "6") (pinfunction "GND_6") (pintype "power_in"))
      (node (ref "U6") (pin "7") (pinfunction "EXP_7") (pintype "power_in"))
    )
    (net (code "34") (name "Net-(D1-PadA)") (class "Default")
      (node (ref "D1") (pin "A") (pinfunction "A_A") (pintype "passive"))
      (node (ref "R15") (pin "2") (pinfunction "2_2") (pintype "passive"))
    )
    (net (code "35") (name "Net-(D2-PadA)") (class "Default")
      (node (ref "D2") (pin "A") (pinfunction "A_A") (pintype "passive"))
      (node (ref "R16") (pin "2") (pinfunction "2_2") (pintype "passive"))
    )
    (net (code "36") (name "Net-(J1-CC1)") (class "Default")
      (node (ref "J1") (pin "3") (pinfunction "CC1_3") (pintype "passive"))
      (node (ref "R7") (pin "1") (pinfunction "1_1") (pintype "passive"))
    )
    (net (code "37") (name "Net-(J1-CC2)") (class "Default")
      (node (ref "J1") (pin "9") (pinfunction "CC2_9") (pintype "passive"))
      (node (ref "R8") (pin "1") (pinfunction "1_1") (pintype "passive"))
    )
    (net (code "38") (name "Net-(J4-Pad-)") (class "Default")
      (node (ref "J4") (pin "-") (pinfunction "-_-") (pintype "passive"))
      (node (ref "J5") (pin "S+1") (pinfunction "+_S+1") (pintype "passive"))
      (node (ref "J5") (pin "S+2") (pinfunction "+_S+2") (pintype "passive"))
    )
    (net (code "39") (name "Net-(Q1-ND1)") (class "Default")
      (node (ref "Q1") (pin "7") (pinfunction "ND1_7") (pintype "bidirectional"))
      (node (ref "Q1") (pin "8") (pinfunction "ND2_8") (pintype "bidirectional"))
      (node (ref "R13") (pin "2") (pinfunction "2_2") (pintype "passive"))
    )
    (net (code "40") (name "Net-(Q1-PG)") (class "Default")
      (node (ref "C20") (pin "1") (pinfunction "1_1") (pintype "passive"))
      (node (ref "Q1") (pin "4") (pinfunction "PG_4") (pintype "bidirectional"))
      (node (ref "R19") (pin "2") (pinfunction "2_2") (pintype "passive"))
      (node (ref "R3") (pin "2") (pinfunction "2_2") (pintype "passive"))
    )
    (net (code "41") (name "Net-(Q3-PG)") (class "Default")
      (node (ref "C10") (pin "1") (pinfunction "1_1") (pintype "passive"))
      (node (ref "Q3") (pin "4") (pinfunction "PG_4") (pintype "bidirectional"))
      (node (ref "R14") (pin "2") (pinfunction "2_2") (pintype "passive"))
      (node (ref "R2") (pin "2") (pinfunction "2_2") (pintype "passive"))
    )
    (net (code "42") (name "Net-(SAW1-IN)") (class "Default")
      (node (ref "SAW1") (pin "P$2") (pinfunction "IN_P$2") (pintype "bidirectional"))
      (node (ref "U2") (pin "7") (pinfunction "ANT_SW_OUT_7") (pintype "bidirectional"))
    )
    (net (code "43") (name "Net-(SAW1-OUT)") (class "Default")
      (node (ref "SAW1") (pin "P$4") (pinfunction "OUT_P$4") (pintype "bidirectional"))
      (node (ref "U2") (pin "11") (pinfunction "MIX_IN_11") (pintype "bidirectional"))
    )
    (net (code "44") (name "Net-(TCXO1-OUT)") (class "Default")
      (node (ref "C6") (pin "2") (pinfunction "2_2") (pintype "passive"))
      (node (ref "TCXO1") (pin "3") (pinfunction "OUT_3") (pintype "bidirectional"))
    )
    (net (code "45") (name "Net-(TCXO1-VDD)") (class "Default")
      (node (ref "C8") (pin "1") (pinfunction "1_1") (pintype "passive"))
      (node (ref "TCXO1") (pin "4") (pinfunction "VDD_4") (pintype "bidirectional"))
      (node (ref "U2") (pin "13") (pinfunction "VCC_TCXO_13") (pintype "bidirectional"))
    )
    (net (code "46") (name "Net-(U1G-DECOUPLE)") (class "Default")
      (node (ref "C11") (pin "1") (pinfunction "1_1") (pintype "passive"))
      (node (ref "U1") (pin "20") (pinfunction "DECOUPLE_20") (pintype "power_in"))
    )
    (net (code "47") (name "Net-(U2-LNA_IN)") (class "Default")
      (node (ref "ANT1") (pin "1") (pinfunction "1_1") (pintype "bidirectional"))
      (node (ref "U2") (pin "4") (pinfunction "LNA_IN_4") (pintype "bidirectional"))
    )
    (net (code "48") (name "Net-(U2-RVI)") (class "Default")
      (node (ref "R1") (pin "1") (pinfunction "1_1") (pintype "passive"))
      (node (ref "U2") (pin "12") (pinfunction "RVI_12") (pintype "bidirectional"))
    )
    (net (code "49") (name "Net-(U2-TCXO_IN)") (class "Default")
      (node (ref "C6") (pin "1") (pinfunction "1_1") (pintype "passive"))
      (node (ref "U2") (pin "15") (pinfunction "TCXO_IN_15") (pintype "bidirectional"))
    )
    (net (code "50") (name "Net-(U2-VAGC)") (class "Default")
      (node (ref "C3") (pin "2") (pinfunction "2_2") (pintype "passive"))
      (node (ref "U2") (pin "1") (pinfunction "VAGC_1") (pintype "bidirectional"))
    )
    (net (code "51") (name "Net-(U3-IO1)") (class "Default")
      (node (ref "J1") (pin "6") (pinfunction "D+_6") (pintype "passive"))
      (node (ref "J1") (pin "7") (pinfunction "D+_7") (pintype "passive"))
      (node (ref "R12") (pin "2") (pinfunction "2_2") (pintype "passive"))
      (node (ref "U3") (pin "P$2") (pinfunction "IO1_P$2") (pintype "bidirectional"))
    )
    (net (code "52") (name "Net-(U3-IO2)") (class "Default")
      (node (ref "J1") (pin "5") (pinfunction "D-_5") (pintype "passive"))
      (node (ref "J1") (pin "8") (pinfunction "D-_8") (pintype "passive"))
      (node (ref "R11") (pin "2") (pinfunction "2_2") (pintype "passive"))
      (node (ref "U3") (pin "P$3") (pinfunction "IO2_P$3") (pintype "bidirectional"))
    )
    (net (code "53") (name "Net-(U3-VCC)") (class "Default")
      (node (ref "J1") (pin "11") (pinfunction "VBUS_11") (pintype "power_in"))
      (node (ref "J1") (pin "2") (pinfunction "VBUS_2") (pintype "power_in"))
      (node (ref "L2") (pin "1") (pinfunction "1_1") (pintype "passive"))
      (node (ref "U3") (pin "P$4") (pinfunction "VCC_P$4") (pintype "bidirectional"))
    )
    (net (code "54") (name "Net-(U6-SW)") (class "Default")
      (node (ref "U6") (pin "1") (pinfunction "SW_1") (pintype "input"))
      (node (ref "U7") (pin "P$2") (pinfunction "P$2_P$2") (pintype "bidirectional"))
    )
    (net (code "55") (name "unconnected-(J1-SBU1-Pad10)") (class "Default")
      (node (ref "J1") (pin "10") (pinfunction "SBU1_10") (pintype "passive"))
    )
    (net (code "56") (name "unconnected-(J1-SBU2-Pad4)") (class "Default")
      (node (ref "J1") (pin "4") (pinfunction "SBU2_4") (pintype "passive"))
    )
    (net (code "57") (name "unconnected-(U1B-PB13{slash}HFXTAL_P{slash}LEUART0_TX#1{slash}USART0_CLK#4,5-Pad12)") (class "Default")
      (node (ref "U1") (pin "12") (pinfunction "PB13/HFXTAL_P/LEUART0_TX#1/USART0_CLK#4,5_12") (pintype "bidirectional"))
    )
    (net (code "58") (name "unconnected-(U2-ANT_BIAS-Pad2)") (class "Default")
      (node (ref "U2") (pin "2") (pinfunction "ANT_BIAS_2") (pintype "bidirectional"))
    )
    (net (code "59") (name "unconnected-(U2-ANT_DET-Pad8)") (class "Default")
      (node (ref "U2") (pin "8") (pinfunction "ANT_DET_8") (pintype "bidirectional"))
    )
    (net (code "60") (name "unconnected-(U2-ANT_IN-Pad3)") (class "Default")
      (node (ref "U2") (pin "3") (pinfunction "ANT_IN_3") (pintype "bidirectional"))
    )
    (net (code "61") (name "unconnected-(U2-MAG-Pad19)") (class "Default")
      (node (ref "U2") (pin "19") (pinfunction "MAG_19") (pintype "bidirectional"))
    )
  )
)
